# Cube_Conector.net
KiCad netlist of a schematic drawn in Altium Designer
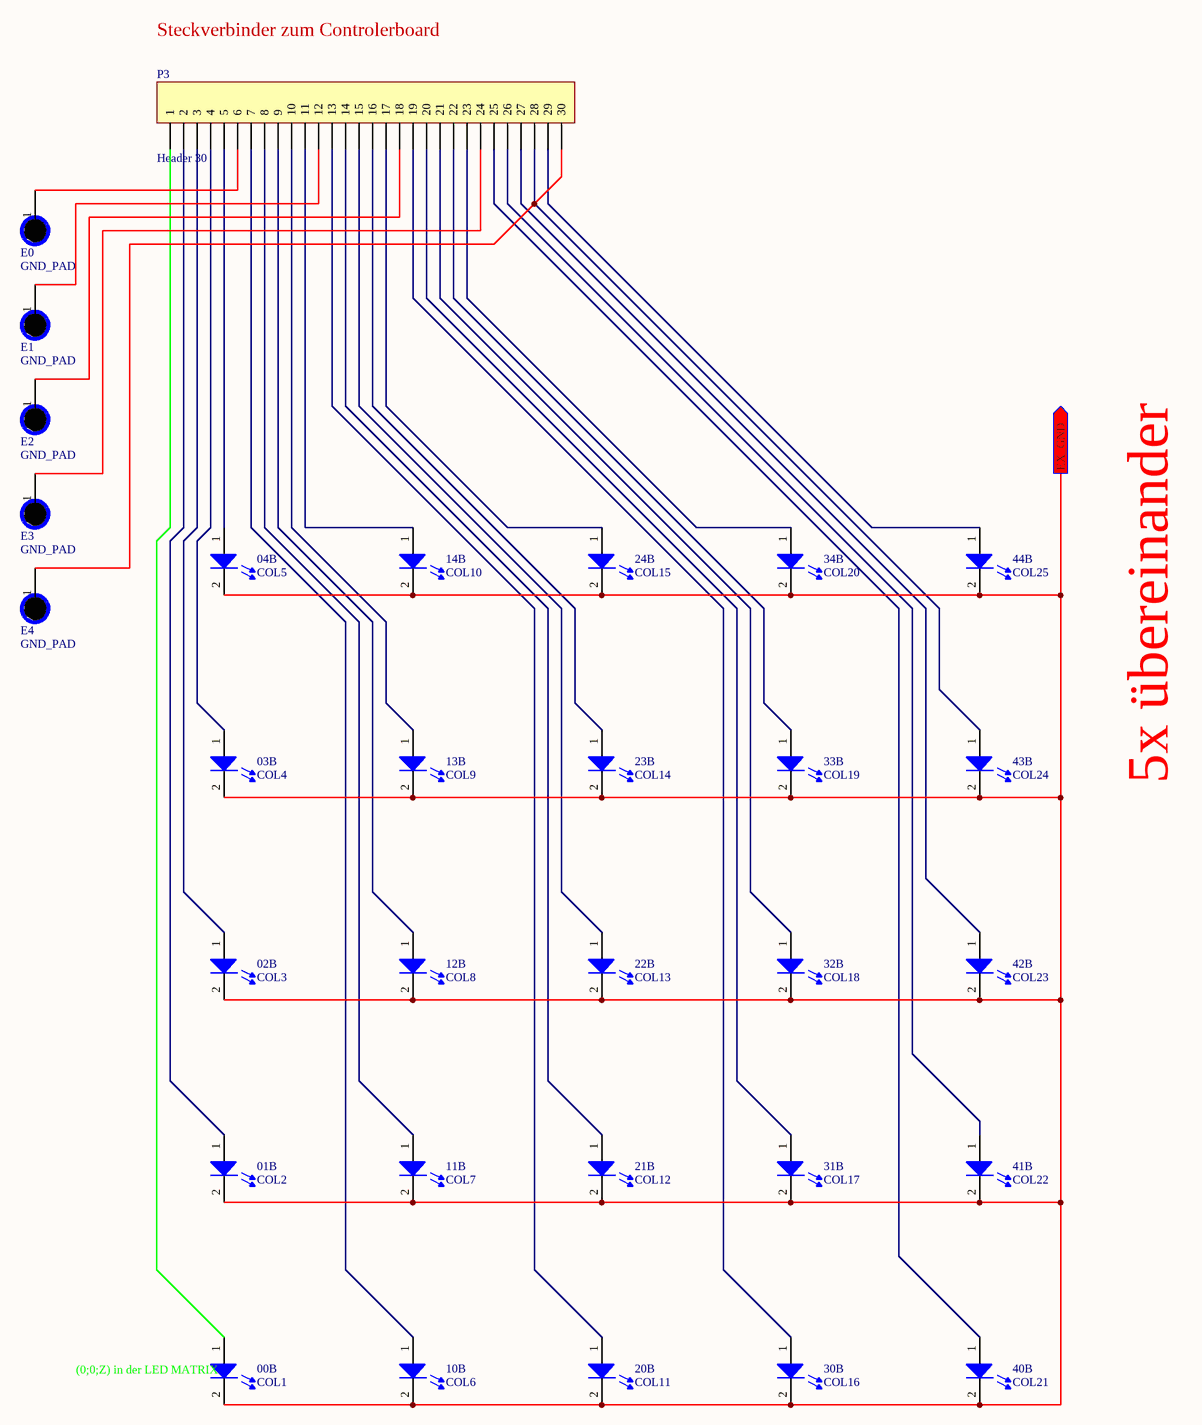
[diagram p0: Cube_Conector.SchDoc]

(export (version "E")
  (design (tool "Eeschema 10.0.6"))
  (components
    (comp (ref "00")
      (value "COL1")
      (footprint "LED 3mm")
      (description "LED bedrahtet")
      (libsource (lib "StdBT") (part "LED Std"))
    )
    (comp (ref "01")
      (value "COL2")
      (footprint "LED 3mm")
      (description "LED bedrahtet")
      (libsource (lib "StdBT") (part "LED Std"))
    )
    (comp (ref "02")
      (value "COL3")
      (footprint "LED 3mm")
      (description "LED bedrahtet")
      (libsource (lib "StdBT") (part "LED Std"))
    )
    (comp (ref "03")
      (value "COL4")
      (footprint "LED 3mm")
      (description "LED bedrahtet")
      (libsource (lib "StdBT") (part "LED Std"))
    )
    (comp (ref "04")
      (value "COL5")
      (footprint "LED 3mm")
      (description "LED bedrahtet")
      (libsource (lib "StdBT") (part "LED Std"))
    )
    (comp (ref "10")
      (value "COL6")
      (footprint "LED 3mm")
      (description "LED bedrahtet")
      (libsource (lib "StdBT") (part "LED Std"))
    )
    (comp (ref "11")
      (value "COL7")
      (footprint "LED 3mm")
      (description "LED bedrahtet")
      (libsource (lib "StdBT") (part "LED Std"))
    )
    (comp (ref "12")
      (value "COL8")
      (footprint "LED 3mm")
      (description "LED bedrahtet")
      (libsource (lib "StdBT") (part "LED Std"))
    )
    (comp (ref "13")
      (value "COL9")
      (footprint "LED 3mm")
      (description "LED bedrahtet")
      (libsource (lib "StdBT") (part "LED Std"))
    )
    (comp (ref "14")
      (value "COL10")
      (footprint "LED 3mm")
      (description "LED bedrahtet")
      (libsource (lib "StdBT") (part "LED Std"))
    )
    (comp (ref "20")
      (value "COL11")
      (footprint "LED 3mm")
      (description "LED bedrahtet")
      (libsource (lib "StdBT") (part "LED Std"))
    )
    (comp (ref "21")
      (value "COL12")
      (footprint "LED 3mm")
      (description "LED bedrahtet")
      (libsource (lib "StdBT") (part "LED Std"))
    )
    (comp (ref "22")
      (value "COL13")
      (footprint "LED 3mm")
      (description "LED bedrahtet")
      (libsource (lib "StdBT") (part "LED Std"))
    )
    (comp (ref "23")
      (value "COL14")
      (footprint "LED 3mm")
      (description "LED bedrahtet")
      (libsource (lib "StdBT") (part "LED Std"))
    )
    (comp (ref "24")
      (value "COL15")
      (footprint "LED 3mm")
      (description "LED bedrahtet")
      (libsource (lib "StdBT") (part "LED Std"))
    )
    (comp (ref "30")
      (value "COL16")
      (footprint "LED 3mm")
      (description "LED bedrahtet")
      (libsource (lib "StdBT") (part "LED Std"))
    )
    (comp (ref "31")
      (value "COL17")
      (footprint "LED 3mm")
      (description "LED bedrahtet")
      (libsource (lib "StdBT") (part "LED Std"))
    )
    (comp (ref "32")
      (value "COL18")
      (footprint "LED 3mm")
      (description "LED bedrahtet")
      (libsource (lib "StdBT") (part "LED Std"))
    )
    (comp (ref "33")
      (value "COL19")
      (footprint "LED 3mm")
      (description "LED bedrahtet")
      (libsource (lib "StdBT") (part "LED Std"))
    )
    (comp (ref "34")
      (value "COL20")
      (footprint "LED 3mm")
      (description "LED bedrahtet")
      (libsource (lib "StdBT") (part "LED Std"))
    )
    (comp (ref "40")
      (value "COL21")
      (footprint "LED 3mm")
      (description "LED bedrahtet")
      (libsource (lib "StdBT") (part "LED Std"))
    )
    (comp (ref "41")
      (value "COL22")
      (footprint "LED 3mm")
      (description "LED bedrahtet")
      (libsource (lib "StdBT") (part "LED Std"))
    )
    (comp (ref "42")
      (value "COL23")
      (footprint "LED 3mm")
      (description "LED bedrahtet")
      (libsource (lib "StdBT") (part "LED Std"))
    )
    (comp (ref "43")
      (value "COL24")
      (footprint "LED 3mm")
      (description "LED bedrahtet")
      (libsource (lib "StdBT") (part "LED Std"))
    )
    (comp (ref "44")
      (value "COL25")
      (footprint "LED 3mm")
      (description "LED bedrahtet")
      (libsource (lib "StdBT") (part "LED Std"))
    )
    (comp (ref "E0") (value "GND_PAD") (footprint "StdBT:GND_PAD") (libsource (lib "StdBT") (part "GND_PAD")))
    (comp (ref "E1") (value "GND_PAD") (footprint "StdBT:GND_PAD") (libsource (lib "StdBT") (part "GND_PAD")))
    (comp (ref "E2") (value "GND_PAD") (footprint "StdBT:GND_PAD") (libsource (lib "StdBT") (part "GND_PAD")))
    (comp (ref "E3") (value "GND_PAD") (footprint "StdBT:GND_PAD") (libsource (lib "StdBT") (part "GND_PAD")))
    (comp (ref "E4") (value "GND_PAD") (footprint "StdBT:GND_PAD") (libsource (lib "StdBT") (part "GND_PAD")))
    (comp (ref "P3")
      (value "Header 30")
      (footprint "HDR1X30")
      (description "Header, 30-Pin")
      (fields (field (name "PUBLISHER") "Altium Limited"))
      (libsource (lib "Miscellaneous Connectors") (part "Header 30"))
    )
  )
  (nets
    (net (code "1") (name "/EX_GND") (class "Default")
      (node (ref "00") (pin "2") (pintype "passive"))
      (node (ref "01") (pin "2") (pintype "passive"))
      (node (ref "02") (pin "2") (pintype "passive"))
      (node (ref "03") (pin "2") (pintype "passive"))
      (node (ref "04") (pin "2") (pintype "passive"))
      (node (ref "10") (pin "2") (pintype "passive"))
      (node (ref "11") (pin "2") (pintype "passive"))
      (node (ref "12") (pin "2") (pintype "passive"))
      (node (ref "13") (pin "2") (pintype "passive"))
      (node (ref "14") (pin "2") (pintype "passive"))
      (node (ref "20") (pin "2") (pintype "passive"))
      (node (ref "21") (pin "2") (pintype "passive"))
      (node (ref "22") (pin "2") (pintype "passive"))
      (node (ref "23") (pin "2") (pintype "passive"))
      (node (ref "24") (pin "2") (pintype "passive"))
      (node (ref "30") (pin "2") (pintype "passive"))
      (node (ref "31") (pin "2") (pintype "passive"))
      (node (ref "32") (pin "2") (pintype "passive"))
      (node (ref "33") (pin "2") (pintype "passive"))
      (node (ref "34") (pin "2") (pintype "passive"))
      (node (ref "40") (pin "2") (pintype "passive"))
      (node (ref "41") (pin "2") (pintype "passive"))
      (node (ref "42") (pin "2") (pintype "passive"))
      (node (ref "43") (pin "2") (pintype "passive"))
      (node (ref "44") (pin "2") (pintype "passive"))
    )
    (net (code "2") (name "Net-(00-Pad1)") (class "Default")
      (node (ref "00") (pin "1") (pintype "passive"))
      (node (ref "P3") (pin "1") (pinfunction "1_1") (pintype "passive"))
    )
    (net (code "3") (name "Net-(01-Pad1)") (class "Default")
      (node (ref "01") (pin "1") (pintype "passive"))
      (node (ref "P3") (pin "2") (pinfunction "2_2") (pintype "passive"))
    )
    (net (code "4") (name "Net-(02-Pad1)") (class "Default")
      (node (ref "02") (pin "1") (pintype "passive"))
      (node (ref "P3") (pin "3") (pinfunction "3_3") (pintype "passive"))
    )
    (net (code "5") (name "Net-(03-Pad1)") (class "Default")
      (node (ref "03") (pin "1") (pintype "passive"))
      (node (ref "P3") (pin "4") (pinfunction "4_4") (pintype "passive"))
    )
    (net (code "6") (name "Net-(04-Pad1)") (class "Default")
      (node (ref "04") (pin "1") (pintype "passive"))
      (node (ref "P3") (pin "5") (pinfunction "5_5") (pintype "passive"))
    )
    (net (code "7") (name "Net-(10-Pad1)") (class "Default")
      (node (ref "10") (pin "1") (pintype "passive"))
      (node (ref "P3") (pin "7") (pinfunction "7_7") (pintype "passive"))
    )
    (net (code "8") (name "Net-(11-Pad1)") (class "Default")
      (node (ref "11") (pin "1") (pintype "passive"))
      (node (ref "P3") (pin "8") (pinfunction "8_8") (pintype "passive"))
    )
    (net (code "9") (name "Net-(12-Pad1)") (class "Default")
      (node (ref "12") (pin "1") (pintype "passive"))
      (node (ref "P3") (pin "9") (pinfunction "9_9") (pintype "passive"))
    )
    (net (code "10") (name "Net-(13-Pad1)") (class "Default")
      (node (ref "13") (pin "1") (pintype "passive"))
      (node (ref "P3") (pin "10") (pinfunction "10_10") (pintype "passive"))
    )
    (net (code "11") (name "Net-(14-Pad1)") (class "Default")
      (node (ref "14") (pin "1") (pintype "passive"))
      (node (ref "P3") (pin "11") (pinfunction "11_11") (pintype "passive"))
    )
    (net (code "12") (name "Net-(20-Pad1)") (class "Default")
      (node (ref "20") (pin "1") (pintype "passive"))
      (node (ref "P3") (pin "13") (pinfunction "13_13") (pintype "passive"))
    )
    (net (code "13") (name "Net-(21-Pad1)") (class "Default")
      (node (ref "21") (pin "1") (pintype "passive"))
      (node (ref "P3") (pin "14") (pinfunction "14_14") (pintype "passive"))
    )
    (net (code "14") (name "Net-(22-Pad1)") (class "Default")
      (node (ref "22") (pin "1") (pintype "passive"))
      (node (ref "P3") (pin "15") (pinfunction "15_15") (pintype "passive"))
    )
    (net (code "15") (name "Net-(23-Pad1)") (class "Default")
      (node (ref "23") (pin "1") (pintype "passive"))
      (node (ref "P3") (pin "16") (pinfunction "16_16") (pintype "passive"))
    )
    (net (code "16") (name "Net-(24-Pad1)") (class "Default")
      (node (ref "24") (pin "1") (pintype "passive"))
      (node (ref "P3") (pin "17") (pinfunction "17_17") (pintype "passive"))
    )
    (net (code "17") (name "Net-(30-Pad1)") (class "Default")
      (node (ref "30") (pin "1") (pintype "passive"))
      (node (ref "P3") (pin "19") (pinfunction "19_19") (pintype "passive"))
    )
    (net (code "18") (name "Net-(31-Pad1)") (class "Default")
      (node (ref "31") (pin "1") (pintype "passive"))
      (node (ref "P3") (pin "20") (pinfunction "20_20") (pintype "passive"))
    )
    (net (code "19") (name "Net-(32-Pad1)") (class "Default")
      (node (ref "32") (pin "1") (pintype "passive"))
      (node (ref "P3") (pin "21") (pinfunction "21_21") (pintype "passive"))
    )
    (net (code "20") (name "Net-(33-Pad1)") (class "Default")
      (node (ref "33") (pin "1") (pintype "passive"))
      (node (ref "P3") (pin "22") (pinfunction "22_22") (pintype "passive"))
    )
    (net (code "21") (name "Net-(34-Pad1)") (class "Default")
      (node (ref "34") (pin "1") (pintype "passive"))
      (node (ref "P3") (pin "23") (pinfunction "23_23") (pintype "passive"))
    )
    (net (code "22") (name "Net-(40-Pad1)") (class "Default")
      (node (ref "40") (pin "1") (pintype "passive"))
      (node (ref "P3") (pin "25") (pinfunction "25_25") (pintype "passive"))
    )
    (net (code "23") (name "Net-(41-Pad1)") (class "Default")
      (node (ref "41") (pin "1") (pintype "passive"))
      (node (ref "P3") (pin "26") (pinfunction "26_26") (pintype "passive"))
    )
    (net (code "24") (name "Net-(42-Pad1)") (class "Default")
      (node (ref "42") (pin "1") (pintype "passive"))
      (node (ref "P3") (pin "27") (pinfunction "27_27") (pintype "passive"))
    )
    (net (code "25") (name "Net-(44-Pad1)") (class "Default")
      (node (ref "44") (pin "1") (pintype "passive"))
      (node (ref "P3") (pin "29") (pinfunction "29_29") (pintype "passive"))
    )
    (net (code "26") (name "Net-(E0-GND)") (class "Default")
      (node (ref "E0") (pin "1") (pinfunction "GND_1") (pintype "passive"))
      (node (ref "P3") (pin "6") (pinfunction "6_6") (pintype "passive"))
    )
    (net (code "27") (name "Net-(E1-GND)") (class "Default")
      (node (ref "E1") (pin "1") (pinfunction "GND_1") (pintype "passive"))
      (node (ref "P3") (pin "12") (pinfunction "12_12") (pintype "passive"))
    )
    (net (code "28") (name "Net-(E2-GND)") (class "Default")
      (node (ref "E2") (pin "1") (pinfunction "GND_1") (pintype "passive"))
      (node (ref "P3") (pin "18") (pinfunction "18_18") (pintype "passive"))
    )
    (net (code "29") (name "Net-(E3-GND)") (class "Default")
      (node (ref "E3") (pin "1") (pinfunction "GND_1") (pintype "passive"))
      (node (ref "P3") (pin "24") (pinfunction "24_24") (pintype "passive"))
    )
    (net (code "30") (name "Net-(E4-GND)") (class "Default")
      (node (ref "43") (pin "1") (pintype "passive"))
      (node (ref "E4") (pin "1") (pinfunction "GND_1") (pintype "passive"))
      (node (ref "P3") (pin "28") (pinfunction "28_28") (pintype "passive"))
      (node (ref "P3") (pin "30") (pinfunction "30_30") (pintype "passive"))
    )
  )
)
